# LDOSchematic.net
KiCad netlist of a schematic drawn in Altium Designer
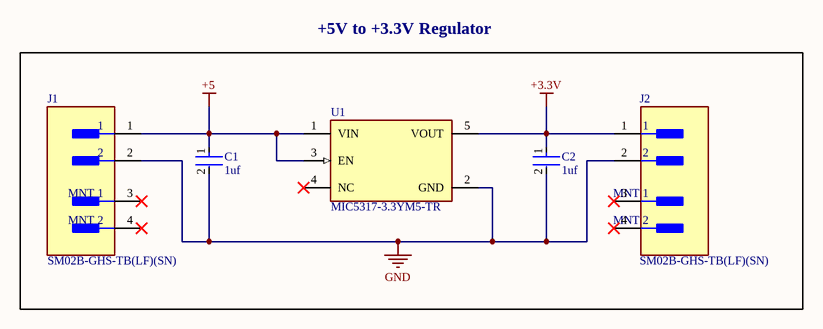
[diagram p0: LDOSchematic.SchDoc]

(export (version "E")
  (design (tool "Eeschema 10.0.6"))
  (components
    (comp (ref "C1")
      (value "1uf")
      (footprint "FP-CC0805-0_85-MFG")
      (description "CAP CER 1UF 10V X7R 0805")
      (fields
        (field (name "MANUFACTURER") "Yageo")
        (field (name "OCTOPART") "https://octopart.com/cc0805kkx7r6bb105-yageo-42522859")
      )
      (libsource (lib "Altium Content Vault") (part "11868f565c42a9108669ba33697ecf6"))
    )
    (comp (ref "C2")
      (value "1uf")
      (footprint "FP-CC0805-0_85-MFG")
      (description "CAP CER 1UF 10V X7R 0805")
      (fields
        (field (name "MANUFACTURER") "Yageo")
        (field (name "OCTOPART") "https://octopart.com/cc0805kkx7r6bb105-yageo-42522859")
      )
      (libsource (lib "Altium Content Vault") (part "11868f565c42a9108669ba33697ecf6"))
    )
    (comp (ref "J1")
      (value "SM02B-GHS-TB(LF)(SN)")
      (footprint "FP-SM02B-GHS-TB_LF_SN-MFG")
      (description "CONN HEADER SMD R/A 2POS 1.25MM")
      (libsource (lib "Altium Content Vault") (part "56ec3178a87b3978bdc1b3682cd516a"))
    )
    (comp (ref "J2")
      (value "SM02B-GHS-TB(LF)(SN)")
      (footprint "FP-SM02B-GHS-TB_LF_SN-MFG")
      (description "CONN HEADER SMD R/A 2POS 1.25MM")
      (libsource (lib "") (part "56ec3178a87b3978bdc1b3682cd516a_1"))
    )
    (comp (ref "U1")
      (value "MIC5317-3.3YM5-TR")
      (footprint "FP-SOT23-5LD-PL-1-MFG")
      (description "IC REG LINEAR 3.3V 150MA SOT23-5")
      (libsource (lib "Altium Content Vault") (part "0a093dae7315cdc977fd108dde87457"))
    )
  )
  (nets
    (net (code "1") (name "+3.3V") (class "Default")
      (node (ref "C2") (pin "1") (pinfunction "1_1") (pintype "passive"))
      (node (ref "J2") (pin "1") (pinfunction "1_1") (pintype "passive"))
      (node (ref "U1") (pin "5") (pinfunction "VOUT_5") (pintype "power_in"))
    )
    (net (code "2") (name "+5") (class "Default")
      (node (ref "C1") (pin "1") (pinfunction "1_1") (pintype "passive"))
      (node (ref "J1") (pin "1") (pinfunction "1_1") (pintype "passive"))
      (node (ref "U1") (pin "1") (pinfunction "VIN_1") (pintype "power_in"))
      (node (ref "U1") (pin "3") (pinfunction "EN_3") (pintype "input"))
    )
    (net (code "3") (name "GND") (class "Default")
      (node (ref "C1") (pin "2") (pinfunction "2_2") (pintype "passive"))
      (node (ref "C2") (pin "2") (pinfunction "2_2") (pintype "passive"))
      (node (ref "J1") (pin "2") (pinfunction "2_2") (pintype "passive"))
      (node (ref "J2") (pin "2") (pinfunction "2_2") (pintype "passive"))
      (node (ref "U1") (pin "2") (pinfunction "GND_2") (pintype "power_in"))
    )
    (net (code "4") (name "unconnected-(J1-MNT_1-Pad3)") (class "Default")
      (node (ref "J1") (pin "3") (pinfunction "MNT_1_3") (pintype "passive+no_connect"))
    )
    (net (code "5") (name "unconnected-(J1-MNT_2-Pad4)") (class "Default")
      (node (ref "J1") (pin "4") (pinfunction "MNT_2_4") (pintype "passive+no_connect"))
    )
    (net (code "6") (name "unconnected-(J2-MNT_1-Pad3)") (class "Default")
      (node (ref "J2") (pin "3") (pinfunction "MNT_1_3") (pintype "passive+no_connect"))
    )
    (net (code "7") (name "unconnected-(J2-MNT_2-Pad4)") (class "Default")
      (node (ref "J2") (pin "4") (pinfunction "MNT_2_4") (pintype "passive+no_connect"))
    )
    (net (code "8") (name "unconnected-(U1-NC-Pad4)") (class "Default")
      (node (ref "U1") (pin "4") (pinfunction "NC_4") (pintype "passive+no_connect"))
    )
  )
)
